# STM32F103-V1_0.net
KiCad netlist of a schematic drawn in Altium Designer
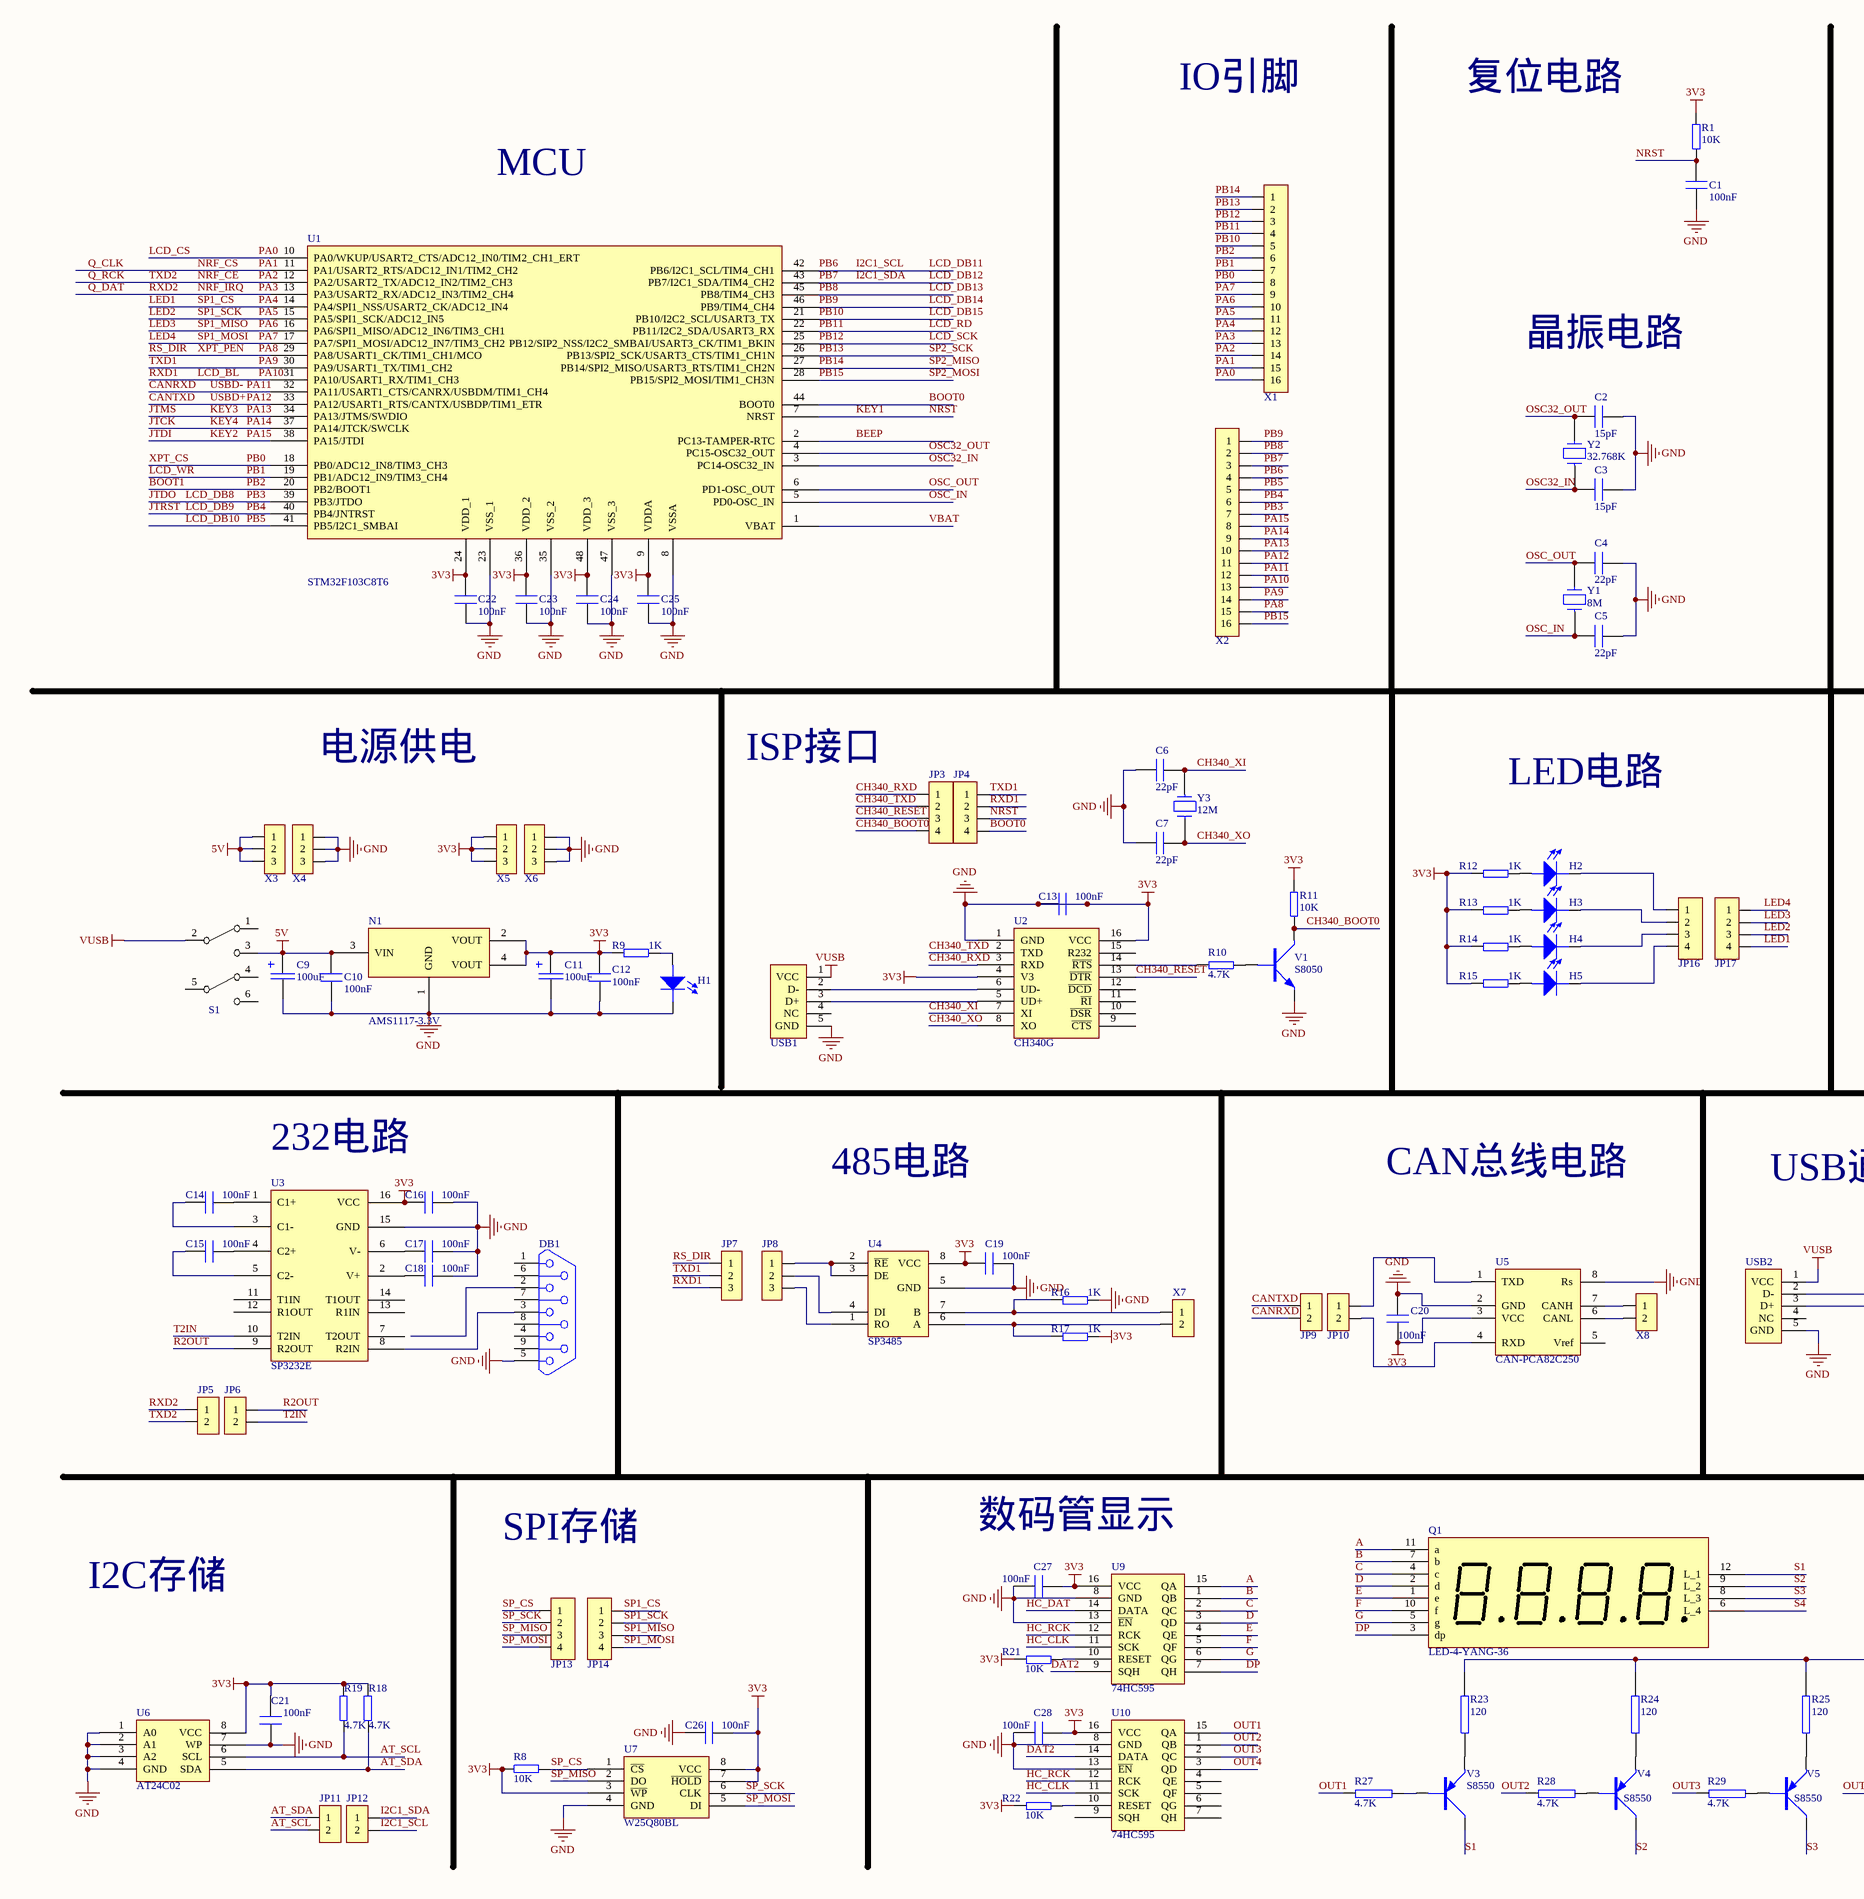
[diagram p0: STM32F103-V1.0.SchDoc, left]
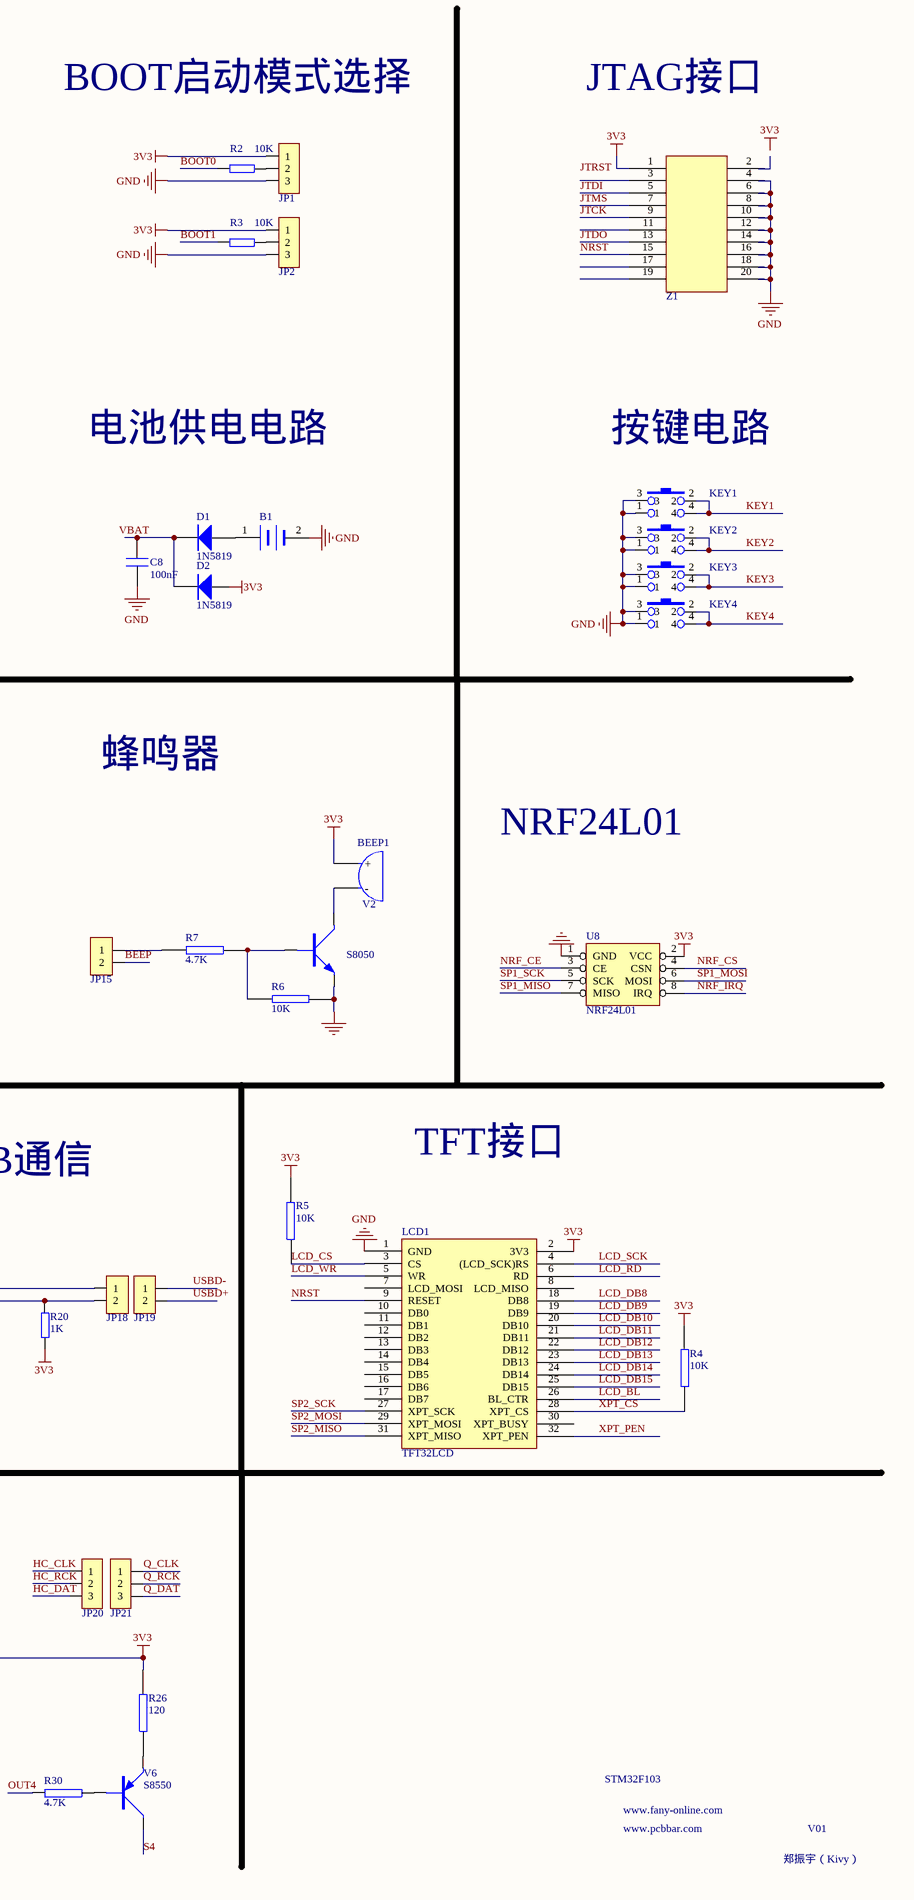
[diagram p1: STM32F103-V1.0.SchDoc, right]

(export (version "E")
  (design (tool "Eeschema 10.0.6"))
  (components
    (comp (ref "B1") (value "BATTERY") (footprint "CR1220") (libsource (lib "Liuzhx") (part "BATTERY")))
    (comp (ref "BEEP1") (value "BEEP") (footprint "SOT12-7.6") (libsource (lib "RationSTM32") (part "BEEP")))
    (comp (ref "C1")
      (value "100nF")
      (footprint "C0805")
      (description "Capacitor")
      (libsource (lib "Liuzhx") (part "普通贴片电容"))
    )
    (comp (ref "C2")
      (value "15pF")
      (footprint "C0805")
      (description "Capacitor")
      (libsource (lib "Liuzhx") (part "普通贴片电容"))
    )
    (comp (ref "C3") (value "15pF") (description "Capacitor") (libsource (lib "Liuzhx") (part "普通贴片电容")))
    (comp (ref "C4") (value "22pF") (description "Capacitor") (libsource (lib "Liuzhx") (part "普通贴片电容")))
    (comp (ref "C5") (value "22pF") (description "Capacitor") (libsource (lib "Liuzhx") (part "普通贴片电容")))
    (comp (ref "C6") (value "22pF") (description "Capacitor") (libsource (lib "Liuzhx") (part "普通贴片电容")))
    (comp (ref "C7")
      (value "22pF")
      (footprint "C0805")
      (description "Capacitor")
      (libsource (lib "Liuzhx") (part "普通贴片电容"))
    )
    (comp (ref "C8")
      (value "100nF")
      (footprint "C0805")
      (description "Capacitor")
      (libsource (lib "Liuzhx") (part "普通贴片电容"))
    )
    (comp (ref "C9") (value "100uF") (footprint "CAP5*5_4") (libsource (lib "Liuzhx") (part "极性电容器")))
    (comp (ref "C10")
      (value "100nF")
      (footprint "C0805")
      (description "Capacitor")
      (libsource (lib "Liuzhx") (part "普通贴片电容"))
    )
    (comp (ref "C11") (value "100uF") (footprint "CAP5*5_4") (libsource (lib "Liuzhx") (part "极性电容器")))
    (comp (ref "C12")
      (value "100nF")
      (footprint "C0805")
      (description "Capacitor")
      (libsource (lib "Liuzhx") (part "普通贴片电容"))
    )
    (comp (ref "C13")
      (value "100nF")
      (footprint "C0805")
      (description "Capacitor")
      (libsource (lib "Liuzhx") (part "普通贴片电容"))
    )
    (comp (ref "C14")
      (value "100nF")
      (footprint "C0805")
      (description "Capacitor")
      (libsource (lib "Liuzhx") (part "普通贴片电容"))
    )
    (comp (ref "C15")
      (value "100nF")
      (footprint "C0805")
      (description "Capacitor")
      (libsource (lib "Liuzhx") (part "普通贴片电容"))
    )
    (comp (ref "C16")
      (value "100nF")
      (footprint "C0805")
      (description "Capacitor")
      (libsource (lib "Liuzhx") (part "普通贴片电容"))
    )
    (comp (ref "C17")
      (value "100nF")
      (footprint "C0805")
      (description "Capacitor")
      (libsource (lib "Liuzhx") (part "普通贴片电容"))
    )
    (comp (ref "C18")
      (value "100nF")
      (footprint "C0805")
      (description "Capacitor")
      (libsource (lib "Liuzhx") (part "普通贴片电容"))
    )
    (comp (ref "C19")
      (value "100nF")
      (footprint "C0805")
      (description "Capacitor")
      (libsource (lib "Liuzhx") (part "普通贴片电容"))
    )
    (comp (ref "C20")
      (value "100nF")
      (footprint "C0805")
      (description "Capacitor")
      (libsource (lib "GKSSCH") (part "普通贴片电容"))
    )
    (comp (ref "C21")
      (value "100nF")
      (footprint "C0805")
      (description "Capacitor")
      (libsource (lib "Liuzhx") (part "普通贴片电容"))
    )
    (comp (ref "C22")
      (value "100nF")
      (footprint "C0805")
      (description "Capacitor")
      (libsource (lib "Liuzhx") (part "普通贴片电容"))
    )
    (comp (ref "C23")
      (value "100nF")
      (footprint "C0805")
      (description "Capacitor")
      (libsource (lib "Liuzhx") (part "普通贴片电容"))
    )
    (comp (ref "C24")
      (value "100nF")
      (footprint "C0805")
      (description "Capacitor")
      (libsource (lib "Liuzhx") (part "普通贴片电容"))
    )
    (comp (ref "C25")
      (value "100nF")
      (footprint "C0805")
      (description "Capacitor")
      (libsource (lib "Liuzhx") (part "普通贴片电容"))
    )
    (comp (ref "C26") (value "100nF") (description "Capacitor") (libsource (lib "Liuzhx") (part "普通贴片电容")))
    (comp (ref "C27") (value "100nF") (description "Capacitor") (libsource (lib "Liuzhx") (part "普通贴片电容")))
    (comp (ref "C28") (value "100nF") (description "Capacitor") (libsource (lib "Liuzhx") (part "普通贴片电容")))
    (comp (ref "D1")
      (value "1N5819")
      (footprint "1N4148-T")
      (description "Diode 1N series")
      (libsource (lib "Liuzhx") (part "贴片二极管"))
    )
    (comp (ref "D2")
      (value "1N5819")
      (footprint "1N4148-T")
      (description "Diode 1N series")
      (libsource (lib "Liuzhx") (part "贴片二极管"))
    )
    (comp (ref "DB1")
      (value "DB9M")
      (footprint "DB9-M")
      (description "母头")
      (libsource (lib "Liuzhx") (part "DB9M"))
    )
    (comp (ref "H1") (value "发光二极管") (footprint "LED1206") (libsource (lib "Liuzhx") (part "发光二极管")))
    (comp (ref "H2") (value "发光二极管") (footprint "LED1206") (libsource (lib "Liuzhx") (part "发光二极管")))
    (comp (ref "H3") (value "发光二极管") (footprint "LED1206") (libsource (lib "Liuzhx") (part "发光二极管")))
    (comp (ref "H4") (value "发光二极管") (footprint "LED1206") (libsource (lib "Liuzhx") (part "发光二极管")))
    (comp (ref "H5") (value "发光二极管") (footprint "LED1206") (libsource (lib "Liuzhx") (part "发光二极管")))
    (comp (ref "JP1")
      (value "JX3")
      (footprint "SIP3")
      (description "Connector")
      (libsource (lib "") (part "JX3_1"))
    )
    (comp (ref "JP2")
      (value "JX3")
      (footprint "SIP3")
      (description "Connector")
      (libsource (lib "") (part "JX3_1"))
    )
    (comp (ref "JP3")
      (value "JX4")
      (footprint "SIP4")
      (description "Connector")
      (libsource (lib "Liuzhx") (part "JX4"))
    )
    (comp (ref "JP4")
      (value "JX4")
      (footprint "SIP4")
      (description "Connector")
      (libsource (lib "") (part "JX4_1"))
    )
    (comp (ref "JP5")
      (value "JX2")
      (footprint "SIP2")
      (description "Connector")
      (libsource (lib "Liuzhx") (part "JX2"))
    )
    (comp (ref "JP6")
      (value "JX2")
      (footprint "SIP2")
      (description "Connector")
      (libsource (lib "") (part "JX2_1"))
    )
    (comp (ref "JP7")
      (value "JX3")
      (footprint "SIP3")
      (description "Connector")
      (libsource (lib "") (part "JX3_1"))
    )
    (comp (ref "JP8")
      (value "JX3")
      (footprint "SIP3")
      (description "Connector")
      (libsource (lib "Liuzhx") (part "JX3"))
    )
    (comp (ref "JP9")
      (value "JX2")
      (footprint "SIP2")
      (description "Connector")
      (libsource (lib "GKSSCH") (part "JX2"))
    )
    (comp (ref "JP10")
      (value "JX2")
      (footprint "SIP2")
      (description "Connector")
      (libsource (lib "") (part "JX2_1"))
    )
    (comp (ref "JP11")
      (value "JX2")
      (footprint "SIP2")
      (description "Connector")
      (libsource (lib "Liuzhx") (part "JX2"))
    )
    (comp (ref "JP12")
      (value "JX2")
      (footprint "SIP2")
      (description "Connector")
      (libsource (lib "") (part "JX2_1"))
    )
    (comp (ref "JP13")
      (value "JX4")
      (footprint "SIP4")
      (description "Connector")
      (libsource (lib "Liuzhx") (part "JX4"))
    )
    (comp (ref "JP14")
      (value "JX4")
      (footprint "SIP4")
      (description "Connector")
      (libsource (lib "") (part "JX4_1"))
    )
    (comp (ref "JP15")
      (value "JX2")
      (footprint "SIP2")
      (description "Connector")
      (libsource (lib "") (part "JX2_1"))
    )
    (comp (ref "JP16")
      (value "JX4")
      (footprint "SIP4")
      (description "Connector")
      (libsource (lib "Liuzhx") (part "JX4"))
    )
    (comp (ref "JP17")
      (value "JX4")
      (footprint "SIP4")
      (description "Connector")
      (libsource (lib "") (part "JX4_1"))
    )
    (comp (ref "JP18")
      (value "JX2")
      (footprint "SIP2")
      (description "Connector")
      (libsource (lib "Liuzhx") (part "JX2"))
    )
    (comp (ref "JP19")
      (value "JX2")
      (footprint "SIP2")
      (description "Connector")
      (libsource (lib "") (part "JX2_1"))
    )
    (comp (ref "JP20")
      (value "JX3")
      (footprint "SIP3")
      (description "Connector")
      (libsource (lib "") (part "JX3_1"))
    )
    (comp (ref "JP21")
      (value "JX3")
      (footprint "SIP3")
      (description "Connector")
      (libsource (lib "Liuzhx") (part "JX3"))
    )
    (comp (ref "KEY1")
      (value "SW-66B7")
      (footprint "STM32F103-V1.0:SW-66")
      (libsource (lib "Liuzhx") (part "SW-66B7"))
    )
    (comp (ref "KEY2")
      (value "SW-66B7")
      (footprint "STM32F103-V1.0:SW-66")
      (libsource (lib "Liuzhx") (part "SW-66B7"))
    )
    (comp (ref "KEY3")
      (value "SW-66B7")
      (footprint "STM32F103-V1.0:SW-66")
      (libsource (lib "Liuzhx") (part "SW-66B7"))
    )
    (comp (ref "KEY4")
      (value "SW-66B7")
      (footprint "STM32F103-V1.0:SW-66")
      (libsource (lib "Liuzhx") (part "SW-66B7"))
    )
    (comp (ref "LCD1") (value "TFT32LCD") (footprint "HEAD16×2") (libsource (lib "Liuzhx") (part "TFT32LCD")))
    (comp (ref "N1")
      (value "AMS1117-3.3V")
      (footprint "SOT223")
      (libsource (lib "Liuzhx") (part "AMS1117-3.3V"))
    )
    (comp (ref "Q1")
      (value "LED-4-YANG-36")
      (footprint "LED0:LED0.36-4")
      (libsource (lib "Liuzhx") (part "LED-4-YANG-36"))
    )
    (comp (ref "R1") (value "10K") (libsource (lib "Liuzhx") (part "普通贴片电阻")))
    (comp (ref "R2") (value "10K") (footprint "R0805") (libsource (lib "Liuzhx") (part "普通贴片电阻")))
    (comp (ref "R3") (value "10K") (footprint "R0805") (libsource (lib "Liuzhx") (part "普通贴片电阻")))
    (comp (ref "R4") (value "10K") (footprint "R0805") (libsource (lib "RationSTM32") (part "RES")))
    (comp (ref "R5") (value "10K") (footprint "R0805") (libsource (lib "RationSTM32") (part "RES")))
    (comp (ref "R6") (value "10K") (footprint "R0805") (libsource (lib "RationSTM32") (part "RES")))
    (comp (ref "R7") (value "4.7K") (footprint "R0805") (libsource (lib "RationSTM32") (part "RES")))
    (comp (ref "R8") (value "10K") (footprint "R0805") (libsource (lib "Liuzhx") (part "普通贴片电阻")))
    (comp (ref "R9") (value "1K") (footprint "R0805") (libsource (lib "Liuzhx") (part "普通贴片电阻")))
    (comp (ref "R10") (value "4.7K") (libsource (lib "Liuzhx") (part "普通贴片电阻")))
    (comp (ref "R11") (value "10K") (libsource (lib "Liuzhx") (part "普通贴片电阻")))
    (comp (ref "R12") (value "1K") (libsource (lib "Liuzhx") (part "普通贴片电阻")))
    (comp (ref "R13") (value "1K") (libsource (lib "Liuzhx") (part "普通贴片电阻")))
    (comp (ref "R14") (value "1K") (footprint "R0805") (libsource (lib "Liuzhx") (part "普通贴片电阻")))
    (comp (ref "R15") (value "1K") (footprint "R0805") (libsource (lib "Liuzhx") (part "普通贴片电阻")))
    (comp (ref "R16") (value "1K") (footprint "R0805") (libsource (lib "Liuzhx") (part "普通贴片电阻")))
    (comp (ref "R17") (value "1K") (footprint "R0805") (libsource (lib "Liuzhx") (part "普通贴片电阻")))
    (comp (ref "R18") (value "4.7K") (footprint "R0805") (libsource (lib "Liuzhx") (part "普通贴片电阻")))
    (comp (ref "R19") (value "4.7K") (footprint "R0805") (libsource (lib "Liuzhx") (part "普通贴片电阻")))
    (comp (ref "R20") (value "1K") (footprint "R0805") (libsource (lib "Liuzhx") (part "普通贴片电阻")))
    (comp (ref "R21") (value "10K") (footprint "R0805") (libsource (lib "Liuzhx") (part "普通贴片电阻")))
    (comp (ref "R22") (value "10K") (footprint "R0805") (libsource (lib "Liuzhx") (part "普通贴片电阻")))
    (comp (ref "R23") (value "120") (footprint "R0805") (libsource (lib "STM32F103-V1.0") (part "RES")))
    (comp (ref "R24") (value "120") (footprint "R0805") (libsource (lib "STM32F103-V1.0") (part "RES")))
    (comp (ref "R25") (value "120") (footprint "R0805") (libsource (lib "STM32F103-V1.0") (part "RES")))
    (comp (ref "R26") (value "120") (footprint "R0805") (libsource (lib "STM32F103-V1.0") (part "RES")))
    (comp (ref "R27") (value "4.7K") (footprint "R0805") (libsource (lib "STM32F103-V1.0") (part "RES2")))
    (comp (ref "R28") (value "4.7K") (footprint "R0805") (libsource (lib "STM32F103-V1.0") (part "RES2")))
    (comp (ref "R29") (value "4.7K") (footprint "R0805") (libsource (lib "STM32F103-V1.0") (part "RES2")))
    (comp (ref "R30") (value "4.7K") (footprint "R0805") (libsource (lib "STM32F103-V1.0") (part "RES2")))
    (comp (ref "S1") (value "SWITCH-6") (footprint "SW-AJ") (libsource (lib "Liuzhx") (part "SWITCH-6")))
    (comp (ref "U1")
      (value "STM32F103C8T6")
      (footprint "LQFP48")
      (libsource (lib "STM32F103-V1.0") (part "STM32F103C8T6"))
    )
    (comp (ref "U2")
      (value "CH340G")
      (footprint "STM32F103-V1.0:SOIC16")
      (libsource (lib "Liuzhx") (part "CH340G"))
    )
    (comp (ref "U3")
      (value "SP3232E")
      (footprint "SOIC16")
      (description "SP3232EEN-L/TR;SOIC-39MM")
      (libsource (lib "Liuzhx") (part "SP3232E"))
    )
    (comp (ref "U4") (value "SP3485") (footprint "SO-8") (libsource (lib "Liuzhx") (part "MAX3082")))
    (comp (ref "U5")
      (value "CAN-PCA82C250")
      (footprint "SO-8")
      (libsource (lib "GKSSCH") (part "CAN-PCA82C250"))
    )
    (comp (ref "U6") (value "AT24C02") (footprint "SO-8") (libsource (lib "Liuzhx") (part "AT24C02")))
    (comp (ref "U7") (value "W25Q80BL") (footprint "W25Q-SO8") (libsource (lib "Liuzhx") (part "W25Q80BL")))
    (comp (ref "U8") (value "NRF24L01") (footprint "NRF24L01") (libsource (lib "Liuzhx") (part "NRF24L01")))
    (comp (ref "U9")
      (value "74HC595")
      (footprint "SO-16")
      (description "串入并出移位寄存器")
      (libsource (lib "Liuzhx") (part "74HC595"))
    )
    (comp (ref "U10")
      (value "74HC595")
      (footprint "SO-16")
      (description "串入并出移位寄存器")
      (libsource (lib "Liuzhx") (part "74HC595"))
    )
    (comp (ref "USB1")
      (value "MicroUSB")
      (footprint "MicroUSB1")
      (description "母头")
      (libsource (lib "Liuzhx") (part "MicroUSB"))
    )
    (comp (ref "USB2")
      (value "MicroUSB")
      (footprint "MicroUSB1")
      (description "母头")
      (libsource (lib "Liuzhx") (part "MicroUSB"))
    )
    (comp (ref "V1")
      (value "S8050")
      (footprint "SOT23-C1")
      (description "V")
      (libsource (lib "Liuzhx") (part "NPN三极管"))
    )
    (comp (ref "V2")
      (value "S8050")
      (footprint "SOT23-C1")
      (description "V")
      (libsource (lib "Liuzhx") (part "NPN三极管"))
    )
    (comp (ref "V3")
      (value "S8550")
      (footprint "SOT23-C1")
      (description "V")
      (libsource (lib "*") (part "PNP三极管"))
    )
    (comp (ref "V4")
      (value "S8550")
      (footprint "SOT23-C1")
      (description "V")
      (libsource (lib "*") (part "PNP三极管"))
    )
    (comp (ref "V5")
      (value "S8550")
      (footprint "SOT23-C1")
      (description "V")
      (libsource (lib "*") (part "PNP三极管"))
    )
    (comp (ref "V6")
      (value "S8550")
      (footprint "SOT23-C1")
      (description "V")
      (libsource (lib "*") (part "PNP三极管"))
    )
    (comp (ref "X1") (value "JX16") (footprint "SIP16") (libsource (lib "Liuzhx") (part "JX16")))
    (comp (ref "X2") (value "JX16") (footprint "SIP16") (libsource (lib "") (part "JX16_1")))
    (comp (ref "X3")
      (value "JX3")
      (footprint "SIP3")
      (description "Connector")
      (libsource (lib "") (part "JX3_1"))
    )
    (comp (ref "X4")
      (value "JX3")
      (footprint "SIP3")
      (description "Connector")
      (libsource (lib "Liuzhx") (part "JX3"))
    )
    (comp (ref "X5")
      (value "JX3")
      (footprint "SIP3")
      (description "Connector")
      (libsource (lib "") (part "JX3_1"))
    )
    (comp (ref "X6")
      (value "JX3")
      (footprint "SIP3")
      (description "Connector")
      (libsource (lib "Liuzhx") (part "JX3"))
    )
    (comp (ref "X7")
      (value "JX2")
      (footprint "WJ128-5.0-2P")
      (description "Connector")
      (libsource (lib "Liuzhx") (part "JX2"))
    )
    (comp (ref "X8")
      (value "JX2")
      (footprint "WJ128-5.0-2P")
      (description "Connector")
      (libsource (lib "GKSSCH") (part "JX2"))
    )
    (comp (ref "Y1")
      (value "8M")
      (footprint "JZ-AX")
      (description "Crystal")
      (libsource (lib "Liuzhx") (part "CRYSTAL"))
    )
    (comp (ref "Y2")
      (value "32.768K")
      (footprint "FC135")
      (description "Crystal")
      (libsource (lib "Liuzhx") (part "CRYSTAL"))
    )
    (comp (ref "Y3")
      (value "12M")
      (footprint "JZ-AX")
      (description "Crystal")
      (libsource (lib "Liuzhx") (part "CRYSTAL"))
    )
    (comp (ref "Z1")
      (value "HEADER 10X2")
      (footprint "JTAG")
      (libsource (lib "STM32F103-V1.0") (part "HEADER 10X2"))
    )
  )
  (nets
    (net (code "1") (name "/A") (class "Default")
      (node (ref "Q1") (pin "11") (pinfunction "a_11") (pintype "passive"))
      (node (ref "U9") (pin "15") (pinfunction "QA_15") (pintype "passive"))
    )
    (net (code "2") (name "/AT_SCL") (class "Default")
      (node (ref "JP11") (pin "2") (pinfunction "2_2") (pintype "passive"))
      (node (ref "R19") (pin "1") (pinfunction "1_1") (pintype "passive"))
      (node (ref "U6") (pin "6") (pinfunction "SCL_6") (pintype "passive"))
    )
    (net (code "3") (name "/AT_SDA") (class "Default")
      (node (ref "JP11") (pin "1") (pinfunction "1_1") (pintype "passive"))
      (node (ref "R18") (pin "1") (pinfunction "1_1") (pintype "passive"))
      (node (ref "U6") (pin "5") (pinfunction "SDA_5") (pintype "passive"))
    )
    (net (code "4") (name "/B") (class "Default")
      (node (ref "Q1") (pin "7") (pinfunction "b_7") (pintype "passive"))
      (node (ref "U9") (pin "1") (pinfunction "QB_1") (pintype "passive"))
    )
    (net (code "5") (name "/BEEP") (class "Default")
      (node (ref "JP15") (pin "2") (pinfunction "2_2") (pintype "passive"))
      (node (ref "U1") (pin "2") (pinfunction "PC13-TAMPER-RTC_2") (pintype "passive"))
    )
    (net (code "6") (name "/BOOT0") (class "Default")
      (node (ref "JP4") (pin "4") (pinfunction "4_4") (pintype "passive"))
      (node (ref "R2") (pin "1") (pinfunction "1_1") (pintype "passive"))
      (node (ref "U1") (pin "44") (pinfunction "BOOT0_44") (pintype "passive"))
    )
    (net (code "7") (name "/BOOT1") (class "Default")
      (node (ref "R3") (pin "1") (pinfunction "1_1") (pintype "passive"))
      (node (ref "U1") (pin "20") (pinfunction "PB2/BOOT1_20") (pintype "passive"))
      (node (ref "X1") (pin "6") (pinfunction "6_6") (pintype "passive"))
    )
    (net (code "8") (name "/C") (class "Default")
      (node (ref "Q1") (pin "4") (pinfunction "c_4") (pintype "passive"))
      (node (ref "U9") (pin "2") (pinfunction "QC_2") (pintype "passive"))
    )
    (net (code "9") (name "/CANRXD") (class "Default")
      (node (ref "JP19") (pin "1") (pinfunction "1_1") (pintype "passive"))
      (node (ref "JP9") (pin "2") (pinfunction "2_2") (pintype "passive"))
      (node (ref "U1") (pin "32") (pinfunction "PA11/USART1_CTS/CANRX/USBDM/TIM1_CH4_32") (pintype "passive"))
      (node (ref "X2") (pin "12") (pinfunction "12_12") (pintype "passive"))
    )
    (net (code "10") (name "/CANTXD") (class "Default")
      (node (ref "JP19") (pin "2") (pinfunction "2_2") (pintype "passive"))
      (node (ref "JP9") (pin "1") (pinfunction "1_1") (pintype "passive"))
      (node (ref "U1") (pin "33") (pinfunction "PA12/USART1_RTS/CANTX/USBDP/TIM1_ETR_33") (pintype "passive"))
      (node (ref "X2") (pin "11") (pinfunction "11_11") (pintype "passive"))
    )
    (net (code "11") (name "/CH340_BOOT0") (class "Default")
      (node (ref "JP3") (pin "4") (pinfunction "4_4") (pintype "passive"))
      (node (ref "R11") (pin "1") (pinfunction "1_1") (pintype "passive"))
      (node (ref "V1") (pin "C") (pinfunction "C_C") (pintype "passive"))
    )
    (net (code "12") (name "/CH340_RESET") (class "Default")
      (node (ref "JP3") (pin "3") (pinfunction "3_3") (pintype "passive"))
      (node (ref "U2") (pin "13") (pinfunction "~{DTR}_13") (pintype "passive"))
    )
    (net (code "13") (name "/CH340_RXD") (class "Default")
      (node (ref "JP3") (pin "1") (pinfunction "1_1") (pintype "passive"))
      (node (ref "U2") (pin "3") (pinfunction "RXD_3") (pintype "passive"))
    )
    (net (code "14") (name "/CH340_TXD") (class "Default")
      (node (ref "JP3") (pin "2") (pinfunction "2_2") (pintype "passive"))
      (node (ref "U2") (pin "2") (pinfunction "TXD_2") (pintype "passive"))
    )
    (net (code "15") (name "/CH340_XI") (class "Default")
      (node (ref "C6") (pin "2") (pinfunction "2_2") (pintype "passive"))
      (node (ref "U2") (pin "7") (pinfunction "XI_7") (pintype "passive"))
      (node (ref "Y3") (pin "1") (pinfunction "1_1") (pintype "passive"))
    )
    (net (code "16") (name "/CH340_XO") (class "Default")
      (node (ref "C7") (pin "2") (pinfunction "2_2") (pintype "passive"))
      (node (ref "U2") (pin "8") (pinfunction "XO_8") (pintype "passive"))
      (node (ref "Y3") (pin "2") (pinfunction "2_2") (pintype "passive"))
    )
    (net (code "17") (name "/D") (class "Default")
      (node (ref "Q1") (pin "2") (pinfunction "d_2") (pintype "passive"))
      (node (ref "U9") (pin "3") (pinfunction "QD_3") (pintype "passive"))
    )
    (net (code "18") (name "/DAT2") (class "Default")
      (node (ref "U10") (pin "14") (pinfunction "DATA_14") (pintype "passive"))
      (node (ref "U9") (pin "9") (pinfunction "SQH_9") (pintype "passive"))
    )
    (net (code "19") (name "/DP") (class "Default")
      (node (ref "Q1") (pin "3") (pinfunction "dp_3") (pintype "passive"))
      (node (ref "U9") (pin "7") (pinfunction "QH_7") (pintype "passive"))
    )
    (net (code "20") (name "/E") (class "Default")
      (node (ref "Q1") (pin "1") (pinfunction "e_1") (pintype "passive"))
      (node (ref "U9") (pin "4") (pinfunction "QE_4") (pintype "passive"))
    )
    (net (code "21") (name "/F") (class "Default")
      (node (ref "Q1") (pin "10") (pinfunction "f_10") (pintype "passive"))
      (node (ref "U9") (pin "5") (pinfunction "QF_5") (pintype "passive"))
    )
    (net (code "22") (name "/G") (class "Default")
      (node (ref "Q1") (pin "5") (pinfunction "g_5") (pintype "passive"))
      (node (ref "U9") (pin "6") (pinfunction "QG_6") (pintype "passive"))
    )
    (net (code "23") (name "/HC_CLK") (class "Default")
      (node (ref "JP20") (pin "1") (pinfunction "1_1") (pintype "passive"))
      (node (ref "U10") (pin "11") (pinfunction "SCK_11") (pintype "passive"))
      (node (ref "U9") (pin "11") (pinfunction "SCK_11") (pintype "passive"))
    )
    (net (code "24") (name "/HC_DAT") (class "Default")
      (node (ref "JP20") (pin "3") (pinfunction "3_3") (pintype "passive"))
      (node (ref "U9") (pin "14") (pinfunction "DATA_14") (pintype "passive"))
    )
    (net (code "25") (name "/HC_RCK") (class "Default")
      (node (ref "JP20") (pin "2") (pinfunction "2_2") (pintype "passive"))
      (node (ref "U10") (pin "12") (pinfunction "RCK_12") (pintype "passive"))
      (node (ref "U9") (pin "12") (pinfunction "RCK_12") (pintype "passive"))
    )
    (net (code "26") (name "/I2C1_SCL") (class "Default")
      (node (ref "JP12") (pin "2") (pinfunction "2_2") (pintype "passive"))
      (node (ref "LCD1") (pin "21") (pinfunction "DB11_21") (pintype "passive"))
      (node (ref "U1") (pin "42") (pinfunction "PB6/I2C1_SCL/TIM4_CH1_42") (pintype "passive"))
      (node (ref "X2") (pin "4") (pinfunction "4_4") (pintype "passive"))
    )
    (net (code "27") (name "/I2C1_SDA") (class "Default")
      (node (ref "JP12") (pin "1") (pinfunction "1_1") (pintype "passive"))
      (node (ref "LCD1") (pin "22") (pinfunction "DB12_22") (pintype "passive"))
      (node (ref "U1") (pin "43") (pinfunction "PB7/I2C1_SDA/TIM4_CH2_43") (pintype "passive"))
      (node (ref "X2") (pin "3") (pinfunction "3_3") (pintype "passive"))
    )
    (net (code "28") (name "/JTCK") (class "Default")
      (node (ref "KEY4") (pin "2") (pinfunction "2_2") (pintype "passive"))
      (node (ref "KEY4") (pin "4") (pinfunction "4_4") (pintype "passive"))
      (node (ref "U1") (pin "37") (pinfunction "PA14/JTCK/SWCLK_37") (pintype "passive"))
      (node (ref "X2") (pin "9") (pinfunction "9_9") (pintype "passive"))
      (node (ref "Z1") (pin "9") (pinfunction "9_9") (pintype "passive"))
    )
    (net (code "29") (name "/JTDI") (class "Default")
      (node (ref "KEY2") (pin "2") (pinfunction "2_2") (pintype "passive"))
      (node (ref "KEY2") (pin "4") (pinfunction "4_4") (pintype "passive"))
      (node (ref "U1") (pin "38") (pinfunction "PA15/JTDI_38") (pintype "passive"))
      (node (ref "X2") (pin "8") (pinfunction "8_8") (pintype "passive"))
      (node (ref "Z1") (pin "5") (pinfunction "5_5") (pintype "passive"))
    )
    (net (code "30") (name "/JTDO") (class "Default")
      (node (ref "LCD1") (pin "18") (pinfunction "DB8_18") (pintype "passive"))
      (node (ref "U1") (pin "39") (pinfunction "PB3/JTDO_39") (pintype "passive"))
      (node (ref "X2") (pin "7") (pinfunction "7_7") (pintype "passive"))
      (node (ref "Z1") (pin "13") (pinfunction "13_13") (pintype "passive"))
    )
    (net (code "31") (name "/JTMS") (class "Default")
      (node (ref "KEY3") (pin "2") (pinfunction "2_2") (pintype "passive"))
      (node (ref "KEY3") (pin "4") (pinfunction "4_4") (pintype "passive"))
      (node (ref "U1") (pin "34") (pinfunction "PA13/JTMS/SWDIO_34") (pintype "passive"))
      (node (ref "X2") (pin "10") (pinfunction "10_10") (pintype "passive"))
      (node (ref "Z1") (pin "7") (pinfunction "7_7") (pintype "passive"))
    )
    (net (code "32") (name "/JTRST") (class "Default")
      (node (ref "LCD1") (pin "19") (pinfunction "DB9_19") (pintype "passive"))
      (node (ref "U1") (pin "40") (pinfunction "PB4/JNTRST_40") (pintype "passive"))
      (node (ref "X2") (pin "6") (pinfunction "6_6") (pintype "passive"))
    )
    (net (code "33") (name "/KEY1") (class "Default")
      (node (ref "C1") (pin "2") (pinfunction "2_2") (pintype "passive"))
      (node (ref "JP4") (pin "3") (pinfunction "3_3") (pintype "passive"))
      (node (ref "KEY1") (pin "2") (pinfunction "2_2") (pintype "passive"))
      (node (ref "KEY1") (pin "4") (pinfunction "4_4") (pintype "passive"))
      (node (ref "LCD1") (pin "9") (pinfunction "RESET_9") (pintype "passive"))
      (node (ref "R1") (pin "1") (pinfunction "1_1") (pintype "passive"))
      (node (ref "U1") (pin "7") (pinfunction "NRST_7") (pintype "passive"))
      (node (ref "Z1") (pin "15") (pinfunction "15_15") (pintype "passive"))
    )
    (net (code "34") (name "/LCD_BL") (class "Default")
      (node (ref "JP4") (pin "2") (pinfunction "2_2") (pintype "passive"))
      (node (ref "JP7") (pin "3") (pinfunction "3_3") (pintype "passive"))
      (node (ref "LCD1") (pin "26") (pinfunction "BL_CTR_26") (pintype "passive"))
      (node (ref "U1") (pin "31") (pinfunction "PA10/USART1_RX/TIM1_CH3_31") (pintype "passive"))
      (node (ref "X2") (pin "13") (pinfunction "13_13") (pintype "passive"))
    )
    (net (code "35") (name "/LCD_CS") (class "Default")
      (node (ref "LCD1") (pin "3") (pinfunction "CS_3") (pintype "passive"))
      (node (ref "R5") (pin "1") (pinfunction "1_1") (pintype "passive"))
      (node (ref "U1") (pin "10") (pinfunction "PA0/WKUP/USART2_CTS/ADC12_IN0/TIM2_CH1_ERT_10") (pintype "passive"))
      (node (ref "X1") (pin "16") (pinfunction "16_16") (pintype "passive"))
    )
    (net (code "36") (name "/LCD_DB10") (class "Default")
      (node (ref "LCD1") (pin "20") (pinfunction "DB10_20") (pintype "passive"))
      (node (ref "U1") (pin "41") (pinfunction "PB5/I2C1_SMBAI_41") (pintype "passive"))
      (node (ref "X2") (pin "5") (pinfunction "5_5") (pintype "passive"))
    )
    (net (code "37") (name "/LCD_DB13") (class "Default")
      (node (ref "LCD1") (pin "23") (pinfunction "DB13_23") (pintype "passive"))
      (node (ref "U1") (pin "45") (pinfunction "PB8/TIM4_CH3_45") (pintype "passive"))
      (node (ref "X2") (pin "2") (pinfunction "2_2") (pintype "passive"))
    )
    (net (code "38") (name "/LCD_DB14") (class "Default")
      (node (ref "LCD1") (pin "24") (pinfunction "DB14_24") (pintype "passive"))
      (node (ref "U1") (pin "46") (pinfunction "PB9/TIM4_CH4_46") (pintype "passive"))
      (node (ref "X2") (pin "1") (pinfunction "1_1") (pintype "passive"))
    )
    (net (code "39") (name "/LCD_DB15") (class "Default")
      (node (ref "LCD1") (pin "25") (pinfunction "DB15_25") (pintype "passive"))
      (node (ref "U1") (pin "21") (pinfunction "PB10/I2C2_SCL/USART3_TX_21") (pintype "passive"))
      (node (ref "X1") (pin "5") (pinfunction "5_5") (pintype "passive"))
    )
    (net (code "40") (name "/LCD_RD") (class "Default")
      (node (ref "LCD1") (pin "6") (pinfunction "RD_6") (pintype "passive"))
      (node (ref "U1") (pin "22") (pinfunction "PB11/I2C2_SDA/USART3_RX_22") (pintype "passive"))
      (node (ref "X1") (pin "4") (pinfunction "4_4") (pintype "passive"))
    )
    (net (code "41") (name "/LCD_SCK") (class "Default")
      (node (ref "LCD1") (pin "4") (pinfunction "(LCD_SCK)RS_4") (pintype "passive"))
      (node (ref "U1") (pin "25") (pinfunction "PB12/SIP2_NSS/I2C2_SMBAI/USART3_CK/TIM1_BKIN_25") (pintype "passive"))
      (node (ref "X1") (pin "3") (pinfunction "3_3") (pintype "passive"))
    )
    (net (code "42") (name "/LCD_WR") (class "Default")
      (node (ref "LCD1") (pin "5") (pinfunction "WR_5") (pintype "passive"))
      (node (ref "U1") (pin "19") (pinfunction "PB1/ADC12_IN9/TIM3_CH4_19") (pintype "passive"))
      (node (ref "X1") (pin "7") (pinfunction "7_7") (pintype "passive"))
    )
    (net (code "43") (name "/LED1") (class "Default")
      (node (ref "JP14") (pin "1") (pinfunction "1_1") (pintype "passive"))
      (node (ref "JP17") (pin "4") (pinfunction "4_4") (pintype "passive"))
      (node (ref "U1") (pin "14") (pinfunction "PA4/SPI1_NSS/USART2_CK/ADC12_IN4_14") (pintype "passive"))
      (node (ref "X1") (pin "12") (pinfunction "12_12") (pintype "passive"))
    )
    (net (code "44") (name "/LED2") (class "Default")
      (node (ref "JP14") (pin "2") (pinfunction "2_2") (pintype "passive"))
      (node (ref "JP17") (pin "3") (pinfunction "3_3") (pintype "passive"))
      (node (ref "U1") (pin "15") (pinfunction "PA5/SPI1_SCK/ADC12_IN5_15") (pintype "passive"))
      (node (ref "U8") (pin "5") (pinfunction "SCK_5") (pintype "passive"))
      (node (ref "X1") (pin "11") (pinfunction "11_11") (pintype "passive"))
    )
    (net (code "45") (name "/LED3") (class "Default")
      (node (ref "JP14") (pin "3") (pinfunction "3_3") (pintype "passive"))
      (node (ref "JP17") (pin "2") (pinfunction "2_2") (pintype "passive"))
      (node (ref "U1") (pin "16") (pinfunction "PA6/SPI1_MISO/ADC12_IN6/TIM3_CH1_16") (pintype "passive"))
      (node (ref "U8") (pin "7") (pinfunction "MISO_7") (pintype "passive"))
      (node (ref "X1") (pin "10") (pinfunction "10_10") (pintype "passive"))
    )
    (net (code "46") (name "/LED4") (class "Default")
      (node (ref "JP14") (pin "4") (pinfunction "4_4") (pintype "passive"))
      (node (ref "JP17") (pin "1") (pinfunction "1_1") (pintype "passive"))
      (node (ref "U1") (pin "17") (pinfunction "PA7/SPI1_MOSI/ADC12_IN7/TIM3_CH2_17") (pintype "passive"))
      (node (ref "U8") (pin "6") (pinfunction "MOSI_6") (pintype "passive"))
      (node (ref "X1") (pin "9") (pinfunction "9_9") (pintype "passive"))
    )
    (net (code "47") (name "/NRF_CE") (class "Default")
      (node (ref "JP21") (pin "2") (pinfunction "2_2") (pintype "passive"))
      (node (ref "JP5") (pin "2") (pinfunction "2_2") (pintype "passive"))
      (node (ref "U1") (pin "12") (pinfunction "PA2/USART2_TX/ADC12_IN2/TIM2_CH3_12") (pintype "passive"))
      (node (ref "U8") (pin "3") (pinfunction "CE_3") (pintype "passive"))
      (node (ref "X1") (pin "14") (pinfunction "14_14") (pintype "passive"))
    )
    (net (code "48") (name "/NRF_CS") (class "Default")
      (node (ref "JP21") (pin "1") (pinfunction "1_1") (pintype "passive"))
      (node (ref "U1") (pin "11") (pinfunction "PA1/USART2_RTS/ADC12_IN1/TIM2_CH2_11") (pintype "passive"))
      (node (ref "U8") (pin "4") (pinfunction "CSN_4") (pintype "passive"))
      (node (ref "X1") (pin "15") (pinfunction "15_15") (pintype "passive"))
    )
    (net (code "49") (name "/NRF_IRQ") (class "Default")
      (node (ref "JP21") (pin "3") (pinfunction "3_3") (pintype "passive"))
      (node (ref "JP5") (pin "1") (pinfunction "1_1") (pintype "passive"))
      (node (ref "U1") (pin "13") (pinfunction "PA3/USART2_RX/ADC12_IN3/TIM2_CH4_13") (pintype "passive"))
      (node (ref "U8") (pin "8") (pinfunction "IRQ_8") (pintype "passive"))
      (node (ref "X1") (pin "13") (pinfunction "13_13") (pintype "passive"))
    )
    (net (code "50") (name "/OSC32_IN") (class "Default")
      (node (ref "C3") (pin "1") (pinfunction "1_1") (pintype "passive"))
      (node (ref "U1") (pin "3") (pinfunction "PC14-OSC32_IN_3") (pintype "passive"))
      (node (ref "Y2") (pin "1") (pinfunction "1_1") (pintype "passive"))
    )
    (net (code "51") (name "/OSC32_OUT") (class "Default")
      (node (ref "C2") (pin "1") (pinfunction "1_1") (pintype "passive"))
      (node (ref "U1") (pin "4") (pinfunction "PC15-OSC32_OUT_4") (pintype "passive"))
      (node (ref "Y2") (pin "2") (pinfunction "2_2") (pintype "passive"))
    )
    (net (code "52") (name "/OSC_IN") (class "Default")
      (node (ref "C5") (pin "1") (pinfunction "1_1") (pintype "passive"))
      (node (ref "U1") (pin "5") (pinfunction "PD0-OSC_IN_5") (pintype "passive"))
      (node (ref "Y1") (pin "1") (pinfunction "1_1") (pintype "passive"))
    )
    (net (code "53") (name "/OSC_OUT") (class "Default")
      (node (ref "C4") (pin "1") (pinfunction "1_1") (pintype "passive"))
      (node (ref "U1") (pin "6") (pinfunction "PD1-OSC_OUT_6") (pintype "passive"))
      (node (ref "Y1") (pin "2") (pinfunction "2_2") (pintype "passive"))
    )
    (net (code "54") (name "/OUT1") (class "Default")
      (node (ref "R27") (pin "1") (pintype "passive"))
      (node (ref "U10") (pin "15") (pinfunction "QA_15") (pintype "passive"))
    )
    (net (code "55") (name "/OUT2") (class "Default")
      (node (ref "R28") (pin "1") (pintype "passive"))
      (node (ref "U10") (pin "1") (pinfunction "QB_1") (pintype "passive"))
    )
    (net (code "56") (name "/OUT3") (class "Default")
      (node (ref "R29") (pin "1") (pintype "passive"))
      (node (ref "U10") (pin "2") (pinfunction "QC_2") (pintype "passive"))
    )
    (net (code "57") (name "/OUT4") (class "Default")
      (node (ref "R30") (pin "1") (pintype "passive"))
      (node (ref "U10") (pin "3") (pinfunction "QD_3") (pintype "passive"))
    )
    (net (code "58") (name "/PA8") (class "Default")
      (node (ref "JP7") (pin "1") (pinfunction "1_1") (pintype "passive"))
      (node (ref "LCD1") (pin "32") (pinfunction "XPT_PEN_32") (pintype "passive"))
      (node (ref "U1") (pin "29") (pinfunction "PA8/USART1_CK/TIM1_CH1/MCO_29") (pintype "passive"))
      (node (ref "X2") (pin "15") (pinfunction "15_15") (pintype "passive"))
    )
    (net (code "59") (name "/PA9") (class "Default")
      (node (ref "JP4") (pin "1") (pinfunction "1_1") (pintype "passive"))
      (node (ref "JP7") (pin "2") (pinfunction "2_2") (pintype "passive"))
      (node (ref "U1") (pin "30") (pinfunction "PA9/USART1_TX/TIM1_CH2_30") (pintype "passive"))
      (node (ref "X2") (pin "14") (pinfunction "14_14") (pintype "passive"))
    )
    (net (code "60") (name "/PB0") (class "Default")
      (node (ref "LCD1") (pin "28") (pinfunction "XPT_CS_28") (pintype "passive"))
      (node (ref "R4") (pin "2") (pinfunction "2_2") (pintype "passive"))
      (node (ref "U1") (pin "18") (pinfunction "PB0/ADC12_IN8/TIM3_CH3_18") (pintype "passive"))
      (node (ref "X1") (pin "8") (pinfunction "8_8") (pintype "passive"))
    )
    (net (code "61") (name "/PB13") (class "Default")
      (node (ref "LCD1") (pin "27") (pinfunction "XPT_SCK_27") (pintype "passive"))
      (node (ref "U1") (pin "26") (pinfunction "PB13/SPI2_SCK/USART3_CTS/TIM1_CH1N_26") (pintype "passive"))
      (node (ref "X1") (pin "2") (pinfunction "2_2") (pintype "passive"))
    )
    (net (code "62") (name "/PB14") (class "Default")
      (node (ref "LCD1") (pin "31") (pinfunction "XPT_MISO_31") (pintype "passive"))
      (node (ref "U1") (pin "27") (pinfunction "PB14/SPI2_MISO/USART3_RTS/TIM1_CH2N_27") (pintype "passive"))
      (node (ref "X1") (pin "1") (pinfunction "1_1") (pintype "passive"))
    )
    (net (code "63") (name "/PB15") (class "Default")
      (node (ref "LCD1") (pin "29") (pinfunction "XPT_MOSI_29") (pintype "passive"))
      (node (ref "U1") (pin "28") (pinfunction "PB15/SPI2_MOSI/TIM1_CH3N_28") (pintype "passive"))
      (node (ref "X2") (pin "16") (pinfunction "16_16") (pintype "passive"))
    )
    (net (code "64") (name "/R2OUT") (class "Default")
      (node (ref "JP6") (pin "1") (pinfunction "1_1") (pintype "passive"))
      (node (ref "U3") (pin "9") (pinfunction "R2OUT_9") (pintype "passive"))
    )
    (net (code "65") (name "/S1") (class "Default")
      (node (ref "Q1") (pin "12") (pinfunction "L_1_12") (pintype "passive"))
      (node (ref "V3") (pin "C") (pinfunction "C_C") (pintype "passive"))
    )
    (net (code "66") (name "/S2") (class "Default")
      (node (ref "Q1") (pin "9") (pinfunction "L_2_9") (pintype "passive"))
      (node (ref "V4") (pin "C") (pinfunction "C_C") (pintype "passive"))
    )
    (net (code "67") (name "/S3") (class "Default")
      (node (ref "Q1") (pin "8") (pinfunction "L_3_8") (pintype "passive"))
      (node (ref "V5") (pin "C") (pinfunction "C_C") (pintype "passive"))
    )
    (net (code "68") (name "/S4") (class "Default")
      (node (ref "Q1") (pin "6") (pinfunction "L_4_6") (pintype "passive"))
      (node (ref "V6") (pin "C") (pinfunction "C_C") (pintype "passive"))
    )
    (net (code "69") (name "/SP_CS") (class "Default")
      (node (ref "JP13") (pin "1") (pinfunction "1_1") (pintype "passive"))
      (node (ref "R8") (pin "1") (pinfunction "1_1") (pintype "passive"))
      (node (ref "U7") (pin "1") (pinfunction "~{CS}_1") (pintype "passive"))
    )
    (net (code "70") (name "/SP_MISO") (class "Default")
      (node (ref "JP13") (pin "3") (pinfunction "3_3") (pintype "passive"))
      (node (ref "U7") (pin "2") (pinfunction "DO_2") (pintype "passive"))
    )
    (net (code "71") (name "/SP_MOSI") (class "Default")
      (node (ref "JP13") (pin "4") (pinfunction "4_4") (pintype "passive"))
      (node (ref "U7") (pin "5") (pinfunction "DI_5") (pintype "passive"))
    )
    (net (code "72") (name "/SP_SCK") (class "Default")
      (node (ref "JP13") (pin "2") (pinfunction "2_2") (pintype "passive"))
      (node (ref "U7") (pin "6") (pinfunction "CLK_6") (pintype "passive"))
    )
    (net (code "73") (name "/T2IN") (class "Default")
      (node (ref "JP6") (pin "2") (pinfunction "2_2") (pintype "passive"))
      (node (ref "U3") (pin "10") (pinfunction "T2IN_10") (pintype "passive"))
    )
    (net (code "74") (name "/VBAT") (class "Default")
      (node (ref "U1") (pin "1") (pinfunction "VBAT_1") (pintype "passive"))
    )
    (net (code "75") (name "3V3") (class "Default")
      (node (ref "B1") (pin "2") (pinfunction "-_2") (pintype "passive"))
      (node (ref "BEEP1") (pin "1") (pinfunction "+_1") (pintype "passive"))
      (node (ref "C1") (pin "1") (pinfunction "1_1") (pintype "passive"))
      (node (ref "C10") (pin "2") (pinfunction "2_2") (pintype "passive"))
      (node (ref "C11") (pin "1") (pinfunction "1_1") (pintype "passive"))
      (node (ref "C11") (pin "2") (pinfunction "2_2") (pintype "passive"))
      (node (ref "C12") (pin "1") (pinfunction "1_1") (pintype "passive"))
      (node (ref "C12") (pin "2") (pinfunction "2_2") (pintype "passive"))
      (node (ref "C13") (pin "1") (pinfunction "1_1") (pintype "passive"))
      (node (ref "C13") (pin "2") (pinfunction "2_2") (pintype "passive"))
      (node (ref "C16") (pin "1") (pinfunction "1_1") (pintype "passive"))
      (node (ref "C16") (pin "2") (pinfunction "2_2") (pintype "passive"))
      (node (ref "C17") (pin "2") (pinfunction "2_2") (pintype "passive"))
      (node (ref "C18") (pin "2") (pinfunction "2_2") (pintype "passive"))
      (node (ref "C19") (pin "1") (pinfunction "1_1") (pintype "passive"))
      (node (ref "C19") (pin "2") (pinfunction "2_2") (pintype "passive"))
      (node (ref "C2") (pin "2") (pinfunction "2_2") (pintype "passive"))
      (node (ref "C20") (pin "1") (pinfunction "1_1") (pintype "passive"))
      (node (ref "C20") (pin "2") (pinfunction "2_2") (pintype "passive"))
      (node (ref "C21") (pin "1") (pinfunction "1_1") (pintype "passive"))
      (node (ref "C21") (pin "2") (pinfunction "2_2") (pintype "passive"))
      (node (ref "C22") (pin "1") (pinfunction "1_1") (pintype "passive"))
      (node (ref "C22") (pin "2") (pinfunction "2_2") (pintype "passive"))
      (node (ref "C23") (pin "1") (pinfunction "1_1") (pintype "passive"))
      (node (ref "C23") (pin "2") (pinfunction "2_2") (pintype "passive"))
      (node (ref "C24") (pin "1") (pinfunction "1_1") (pintype "passive"))
      (node (ref "C24") (pin "2") (pinfunction "2_2") (pintype "passive"))
      (node (ref "C25") (pin "1") (pinfunction "1_1") (pintype "passive"))
      (node (ref "C25") (pin "2") (pinfunction "2_2") (pintype "passive"))
      (node (ref "C26") (pin "1") (pinfunction "1_1") (pintype "passive"))
      (node (ref "C26") (pin "2") (pinfunction "2_2") (pintype "passive"))
      (node (ref "C27") (pin "1") (pinfunction "1_1") (pintype "passive"))
      (node (ref "C27") (pin "2") (pinfunction "2_2") (pintype "passive"))
      (node (ref "C28") (pin "1") (pinfunction "1_1") (pintype "passive"))
      (node (ref "C28") (pin "2") (pinfunction "2_2") (pintype "passive"))
      (node (ref "C3") (pin "2") (pinfunction "2_2") (pintype "passive"))
      (node (ref "C4") (pin "2") (pinfunction "2_2") (pintype "passive"))
      (node (ref "C5") (pin "2") (pinfunction "2_2") (pintype "passive"))
      (node (ref "C6") (pin "1") (pinfunction "1_1") (pintype "passive"))
      (node (ref "C7") (pin "1") (pinfunction "1_1") (pintype "passive"))
      (node (ref "C8") (pin "1") (pinfunction "1_1") (pintype "passive"))
      (node (ref "C9") (pin "2") (pinfunction "2_2") (pintype "passive"))
      (node (ref "DB1") (pin "5") (pinfunction "5_5") (pintype "passive"))
      (node (ref "H1") (pin "2") (pinfunction "K_2") (pintype "passive"))
      (node (ref "JP1") (pin "1") (pinfunction "1_1") (pintype "passive"))
      (node (ref "JP1") (pin "3") (pinfunction "3_3") (pintype "passive"))
      (node (ref "JP2") (pin "1") (pinfunction "1_1") (pintype "passive"))
      (node (ref "JP2") (pin "3") (pinfunction "3_3") (pintype "passive"))
      (node (ref "KEY1") (pin "1") (pinfunction "1_1") (pintype "passive"))
      (node (ref "KEY1") (pin "3") (pinfunction "3_3") (pintype "passive"))
      (node (ref "KEY2") (pin "1") (pinfunction "1_1") (pintype "passive"))
      (node (ref "KEY2") (pin "3") (pinfunction "3_3") (pintype "passive"))
      (node (ref "KEY3") (pin "1") (pinfunction "1_1") (pintype "passive"))
      (node (ref "KEY3") (pin "3") (pinfunction "3_3") (pintype "passive"))
      (node (ref "KEY4") (pin "1") (pinfunction "1_1") (pintype "passive"))
      (node (ref "KEY4") (pin "3") (pinfunction "3_3") (pintype "passive"))
      (node (ref "LCD1") (pin "1") (pinfunction "GND_1") (pintype "passive"))
      (node (ref "LCD1") (pin "2") (pinfunction "3V3_2") (pintype "passive"))
      (node (ref "N1") (pin "1") (pinfunction "GND_1") (pintype "passive"))
      (node (ref "N1") (pin "2") (pinfunction "VOUT_2") (pintype "passive"))
      (node (ref "N1") (pin "4") (pinfunction "VOUT_4") (pintype "passive"))
      (node (ref "R1") (pin "2") (pinfunction "2_2") (pintype "passive"))
      (node (ref "R11") (pin "2") (pinfunction "2_2") (pintype "passive"))
      (node (ref "R12") (pin "1") (pinfunction "1_1") (pintype "passive"))
      (node (ref "R13") (pin "1") (pinfunction "1_1") (pintype "passive"))
      (node (ref "R14") (pin "1") (pinfunction "1_1") (pintype "passive"))
      (node (ref "R15") (pin "1") (pinfunction "1_1") (pintype "passive"))
      (node (ref "R16") (pin "2") (pinfunction "2_2") (pintype "passive"))
      (node (ref "R17") (pin "2") (pinfunction "2_2") (pintype "passive"))
      (node (ref "R18") (pin "2") (pinfunction "2_2") (pintype "passive"))
      (node (ref "R19") (pin "2") (pinfunction "2_2") (pintype "passive"))
      (node (ref "R20") (pin "2") (pinfunction "2_2") (pintype "passive"))
      (node (ref "R21") (pin "1") (pinfunction "1_1") (pintype "passive"))
      (node (ref "R22") (pin "1") (pinfunction "1_1") (pintype "passive"))
      (node (ref "R23") (pin "2") (pinfunction "2_2") (pintype "passive"))
      (node (ref "R24") (pin "2") (pinfunction "2_2") (pintype "passive"))
      (node (ref "R25") (pin "2") (pinfunction "2_2") (pintype "passive"))
      (node (ref "R26") (pin "2") (pinfunction "2_2") (pintype "passive"))
      (node (ref "R4") (pin "1") (pinfunction "1_1") (pintype "passive"))
      (node (ref "R5") (pin "2") (pinfunction "2_2") (pintype "passive"))
      (node (ref "R6") (pin "1") (pinfunction "1_1") (pintype "passive"))
      (node (ref "R8") (pin "2") (pinfunction "2_2") (pintype "passive"))
      (node (ref "R9") (pin "1") (pinfunction "1_1") (pintype "passive"))
      (node (ref "U1") (pin "23") (pinfunction "VSS_1_23") (pintype "passive"))
      (node (ref "U1") (pin "24") (pinfunction "VDD_1_24") (pintype "passive"))
      (node (ref "U1") (pin "35") (pinfunction "VSS_2_35") (pintype "passive"))
      (node (ref "U1") (pin "36") (pinfunction "VDD_2_36") (pintype "passive"))
      (node (ref "U1") (pin "47") (pinfunction "VSS_3_47") (pintype "passive"))
      (node (ref "U1") (pin "48") (pinfunction "VDD_3_48") (pintype "passive"))
      (node (ref "U1") (pin "8") (pinfunction "VSSA_8") (pintype "passive"))
      (node (ref "U1") (pin "9") (pinfunction "VDDA_9") (pintype "passive"))
      (node (ref "U10") (pin "13") (pinfunction "~{EN}_13") (pintype "passive"))
      (node (ref "U10") (pin "16") (pinfunction "VCC_16") (pintype "passive"))
      (node (ref "U10") (pin "8") (pinfunction "GND_8") (pintype "passive"))
      (node (ref "U2") (pin "1") (pinfunction "GND_1") (pintype "passive"))
      (node (ref "U2") (pin "16") (pinfunction "VCC_16") (pintype "passive"))
      (node (ref "U2") (pin "4") (pinfunction "V3_4") (pintype "passive"))
      (node (ref "U3") (pin "15") (pinfunction "GND_15") (pintype "passive"))
      (node (ref "U3") (pin "16") (pinfunction "VCC_16") (pintype "passive"))
      (node (ref "U4") (pin "5") (pinfunction "GND_5") (pintype "passive"))
      (node (ref "U4") (pin "8") (pinfunction "VCC_8") (pintype "passive"))
      (node (ref "U5") (pin "2") (pinfunction "GND_2") (pintype "passive"))
      (node (ref "U5") (pin "3") (pinfunction "VCC_3") (pintype "passive"))
      (node (ref "U5") (pin "8") (pinfunction "Rs_8") (pintype "passive"))
      (node (ref "U6") (pin "1") (pinfunction "A0_1") (pintype "passive"))
      (node (ref "U6") (pin "2") (pinfunction "A1_2") (pintype "passive"))
      (node (ref "U6") (pin "3") (pinfunction "A2_3") (pintype "passive"))
      (node (ref "U6") (pin "4") (pinfunction "GND_4") (pintype "passive"))
      (node (ref "U6") (pin "7") (pinfunction "WP_7") (pintype "passive"))
      (node (ref "U6") (pin "8") (pinfunction "VCC_8") (pintype "passive"))
      (node (ref "U7") (pin "3") (pinfunction "~{WP}_3") (pintype "passive"))
      (node (ref "U7") (pin "4") (pinfunction "GND_4") (pintype "passive"))
      (node (ref "U7") (pin "7") (pinfunction "~{HOLD}_7") (pintype "passive"))
      (node (ref "U7") (pin "8") (pinfunction "VCC_8") (pintype "passive"))
      (node (ref "U8") (pin "1") (pinfunction "GND_1") (pintype "passive"))
      (node (ref "U8") (pin "2") (pinfunction "VCC_2") (pintype "passive"))
      (node (ref "U9") (pin "13") (pinfunction "~{EN}_13") (pintype "passive"))
      (node (ref "U9") (pin "16") (pinfunction "VCC_16") (pintype "passive"))
      (node (ref "U9") (pin "8") (pinfunction "GND_8") (pintype "passive"))
      (node (ref "USB1") (pin "5") (pinfunction "GND_5") (pintype "passive"))
      (node (ref "USB2") (pin "5") (pinfunction "GND_5") (pintype "passive"))
      (node (ref "V1") (pin "E") (pinfunction "E_E") (pintype "passive"))
      (node (ref "V2") (pin "E") (pinfunction "E_E") (pintype "passive"))
      (node (ref "X4") (pin "1") (pinfunction "1_1") (pintype "passive"))
      (node (ref "X4") (pin "2") (pinfunction "2_2") (pintype "passive"))
      (node (ref "X4") (pin "3") (pinfunction "3_3") (pintype "passive"))
      (node (ref "X5") (pin "1") (pinfunction "1_1") (pintype "passive"))
      (node (ref "X5") (pin "2") (pinfunction "2_2") (pintype "passive"))
      (node (ref "X5") (pin "3") (pinfunction "3_3") (pintype "passive"))
      (node (ref "X6") (pin "1") (pinfunction "1_1") (pintype "passive"))
      (node (ref "X6") (pin "2") (pinfunction "2_2") (pintype "passive"))
      (node (ref "X6") (pin "3") (pinfunction "3_3") (pintype "passive"))
      (node (ref "Z1") (pin "1") (pinfunction "1_1") (pintype "passive"))
    )
    (net (code "76") (name "5V") (class "Default")
      (node (ref "C10") (pin "1") (pinfunction "1_1") (pintype "passive"))
      (node (ref "C9") (pin "1") (pinfunction "1_1") (pintype "passive"))
      (node (ref "N1") (pin "3") (pinfunction "VIN_3") (pintype "passive"))
      (node (ref "S1") (pin "3") (pintype "passive"))
      (node (ref "X3") (pin "1") (pinfunction "1_1") (pintype "passive"))
      (node (ref "X3") (pin "2") (pinfunction "2_2") (pintype "passive"))
      (node (ref "X3") (pin "3") (pinfunction "3_3") (pintype "passive"))
    )
    (net (code "77") (name "Net-(B1-+)") (class "Default")
      (node (ref "B1") (pin "1") (pinfunction "+_1") (pintype "passive"))
      (node (ref "D1") (pin "1") (pinfunction "A_1") (pintype "passive"))
    )
    (net (code "78") (name "Net-(BEEP1--)") (class "Default")
      (node (ref "BEEP1") (pin "2") (pinfunction "-_2") (pintype "passive"))
      (node (ref "V2") (pin "C") (pinfunction "C_C") (pintype "passive"))
    )
    (net (code "79") (name "Net-(D1-K)") (class "Default")
      (node (ref "C8") (pin "2") (pinfunction "2_2") (pintype "passive"))
      (node (ref "D1") (pin "2") (pinfunction "K_2") (pintype "passive"))
      (node (ref "D2") (pin "2") (pinfunction "K_2") (pintype "passive"))
    )
    (net (code "80") (name "Net-(H1-A)") (class "Default")
      (node (ref "H1") (pin "1") (pinfunction "A_1") (pintype "passive"))
      (node (ref "R9") (pin "2") (pinfunction "2_2") (pintype "passive"))
    )
    (net (code "81") (name "Net-(H2-A)") (class "Default")
      (node (ref "H2") (pin "1") (pinfunction "A_1") (pintype "passive"))
      (node (ref "R12") (pin "2") (pinfunction "2_2") (pintype "passive"))
    )
    (net (code "82") (name "Net-(H2-K)") (class "Default")
      (node (ref "H2") (pin "2") (pinfunction "K_2") (pintype "passive"))
      (node (ref "JP16") (pin "1") (pinfunction "1_1") (pintype "passive"))
    )
    (net (code "83") (name "Net-(H3-A)") (class "Default")
      (node (ref "H3") (pin "1") (pinfunction "A_1") (pintype "passive"))
      (node (ref "R13") (pin "2") (pinfunction "2_2") (pintype "passive"))
    )
    (net (code "84") (name "Net-(H3-K)") (class "Default")
      (node (ref "H3") (pin "2") (pinfunction "K_2") (pintype "passive"))
      (node (ref "JP16") (pin "2") (pinfunction "2_2") (pintype "passive"))
    )
    (net (code "85") (name "Net-(H4-A)") (class "Default")
      (node (ref "H4") (pin "1") (pinfunction "A_1") (pintype "passive"))
      (node (ref "R14") (pin "2") (pinfunction "2_2") (pintype "passive"))
    )
    (net (code "86") (name "Net-(H4-K)") (class "Default")
      (node (ref "H4") (pin "2") (pinfunction "K_2") (pintype "passive"))
      (node (ref "JP16") (pin "3") (pinfunction "3_3") (pintype "passive"))
    )
    (net (code "87") (name "Net-(H5-A)") (class "Default")
      (node (ref "H5") (pin "1") (pinfunction "A_1") (pintype "passive"))
      (node (ref "R15") (pin "2") (pinfunction "2_2") (pintype "passive"))
    )
    (net (code "88") (name "Net-(H5-K)") (class "Default")
      (node (ref "H5") (pin "2") (pinfunction "K_2") (pintype "passive"))
      (node (ref "JP16") (pin "4") (pinfunction "4_4") (pintype "passive"))
    )
    (net (code "89") (name "Net-(JP1-Pad2)") (class "Default")
      (node (ref "JP1") (pin "2") (pinfunction "2_2") (pintype "passive"))
      (node (ref "R2") (pin "2") (pinfunction "2_2") (pintype "passive"))
    )
    (net (code "90") (name "Net-(JP2-Pad2)") (class "Default")
      (node (ref "JP2") (pin "2") (pinfunction "2_2") (pintype "passive"))
      (node (ref "R3") (pin "2") (pinfunction "2_2") (pintype "passive"))
    )
    (net (code "91") (name "Net-(JP15-Pad1)") (class "Default")
      (node (ref "JP15") (pin "1") (pinfunction "1_1") (pintype "passive"))
      (node (ref "R7") (pin "1") (pinfunction "1_1") (pintype "passive"))
    )
    (net (code "92") (name "Net-(R6-Pad2)") (class "Default")
      (node (ref "R6") (pin "2") (pinfunction "2_2") (pintype "passive"))
      (node (ref "R7") (pin "2") (pinfunction "2_2") (pintype "passive"))
      (node (ref "V2") (pin "B") (pinfunction "B_B") (pintype "passive"))
    )
    (net (code "93") (name "Net-(R10-Pad2)") (class "Default")
      (node (ref "R10") (pin "2") (pinfunction "2_2") (pintype "passive"))
      (node (ref "V1") (pin "B") (pinfunction "B_B") (pintype "passive"))
    )
    (net (code "94") (name "Net-(R23-Pad1)") (class "Default")
      (node (ref "R23") (pin "1") (pinfunction "1_1") (pintype "passive"))
      (node (ref "V3") (pin "E") (pinfunction "E_E") (pintype "passive"))
    )
    (net (code "95") (name "Net-(R24-Pad1)") (class "Default")
      (node (ref "R24") (pin "1") (pinfunction "1_1") (pintype "passive"))
      (node (ref "V4") (pin "E") (pinfunction "E_E") (pintype "passive"))
    )
    (net (code "96") (name "Net-(R25-Pad1)") (class "Default")
      (node (ref "R25") (pin "1") (pinfunction "1_1") (pintype "passive"))
      (node (ref "V5") (pin "E") (pinfunction "E_E") (pintype "passive"))
    )
    (net (code "97") (name "Net-(R26-Pad1)") (class "Default")
      (node (ref "R26") (pin "1") (pinfunction "1_1") (pintype "passive"))
      (node (ref "V6") (pin "E") (pinfunction "E_E") (pintype "passive"))
    )
    (net (code "98") (name "Net-(R27-Pad2)") (class "Default")
      (node (ref "R27") (pin "2") (pintype "passive"))
      (node (ref "V3") (pin "B") (pinfunction "B_B") (pintype "passive"))
    )
    (net (code "99") (name "Net-(R28-Pad2)") (class "Default")
      (node (ref "R28") (pin "2") (pintype "passive"))
      (node (ref "V4") (pin "B") (pinfunction "B_B") (pintype "passive"))
    )
    (net (code "100") (name "Net-(R29-Pad2)") (class "Default")
      (node (ref "R29") (pin "2") (pintype "passive"))
      (node (ref "V5") (pin "B") (pinfunction "B_B") (pintype "passive"))
    )
    (net (code "101") (name "Net-(R30-Pad2)") (class "Default")
      (node (ref "R30") (pin "2") (pintype "passive"))
      (node (ref "V6") (pin "B") (pinfunction "B_B") (pintype "passive"))
    )
    (net (code "102") (name "Net-(U2-UD+)") (class "Default")
      (node (ref "U2") (pin "5") (pinfunction "UD+_5") (pintype "passive"))
      (node (ref "USB1") (pin "3") (pinfunction "D+_3") (pintype "passive"))
    )
    (net (code "103") (name "Net-(U2-UD-)") (class "Default")
      (node (ref "U2") (pin "6") (pinfunction "UD-_6") (pintype "passive"))
      (node (ref "USB1") (pin "2") (pinfunction "D-_2") (pintype "passive"))
    )
    (net (code "104") (name "Net-(U2-~{RTS})") (class "Default")
      (node (ref "R10") (pin "1") (pinfunction "1_1") (pintype "passive"))
      (node (ref "U2") (pin "14") (pinfunction "~{RTS}_14") (pintype "passive"))
    )
    (net (code "105") (name "Net-(U3-C1+)") (class "Default")
      (node (ref "C14") (pin "2") (pinfunction "2_2") (pintype "passive"))
      (node (ref "U3") (pin "1") (pinfunction "C1+_1") (pintype "passive"))
    )
    (net (code "106") (name "Net-(U3-C1-)") (class "Default")
      (node (ref "C14") (pin "1") (pinfunction "1_1") (pintype "passive"))
      (node (ref "U3") (pin "3") (pinfunction "C1-_3") (pintype "passive"))
    )
    (net (code "107") (name "Net-(U3-C2+)") (class "Default")
      (node (ref "C15") (pin "2") (pinfunction "2_2") (pintype "passive"))
      (node (ref "U3") (pin "4") (pinfunction "C2+_4") (pintype "passive"))
    )
    (net (code "108") (name "Net-(U3-C2-)") (class "Default")
      (node (ref "C15") (pin "1") (pinfunction "1_1") (pintype "passive"))
      (node (ref "U3") (pin "5") (pinfunction "C2-_5") (pintype "passive"))
    )
    (net (code "109") (name "Net-(U3-R2IN)") (class "Default")
      (node (ref "DB1") (pin "3") (pinfunction "3_3") (pintype "passive"))
      (node (ref "U3") (pin "8") (pinfunction "R2IN_8") (pintype "passive"))
    )
    (net (code "110") (name "Net-(U3-V+)") (class "Default")
      (node (ref "C18") (pin "1") (pinfunction "1_1") (pintype "passive"))
      (node (ref "U3") (pin "2") (pinfunction "V+_2") (pintype "passive"))
    )
    (net (code "111") (name "Net-(U3-V-)") (class "Default")
      (node (ref "C17") (pin "1") (pinfunction "1_1") (pintype "passive"))
      (node (ref "U3") (pin "6") (pinfunction "V-_6") (pintype "passive"))
    )
    (net (code "112") (name "Net-(U4-A)") (class "Default")
      (node (ref "R17") (pin "1") (pinfunction "1_1") (pintype "passive"))
      (node (ref "U4") (pin "6") (pinfunction "A_6") (pintype "passive"))
      (node (ref "X7") (pin "2") (pinfunction "2_2") (pintype "passive"))
    )
    (net (code "113") (name "Net-(U4-B)") (class "Default")
      (node (ref "R16") (pin "1") (pinfunction "1_1") (pintype "passive"))
      (node (ref "U4") (pin "7") (pinfunction "B_7") (pintype "passive"))
      (node (ref "X7") (pin "1") (pinfunction "1_1") (pintype "passive"))
    )
    (net (code "114") (name "Net-(U4-DE)") (class "Default")
      (node (ref "JP8") (pin "1") (pinfunction "1_1") (pintype "passive"))
      (node (ref "U4") (pin "2") (pinfunction "~{RE}_2") (pintype "passive"))
      (node (ref "U4") (pin "3") (pinfunction "DE_3") (pintype "passive"))
    )
    (net (code "115") (name "Net-(U4-DI)") (class "Default")
      (node (ref "JP8") (pin "2") (pinfunction "2_2") (pintype "passive"))
      (node (ref "U4") (pin "4") (pinfunction "DI_4") (pintype "passive"))
    )
    (net (code "116") (name "Net-(U4-RO)") (class "Default")
      (node (ref "JP8") (pin "3") (pinfunction "3_3") (pintype "passive"))
      (node (ref "U4") (pin "1") (pinfunction "RO_1") (pintype "passive"))
    )
    (net (code "117") (name "Net-(U5-CANH)") (class "Default")
      (node (ref "U5") (pin "7") (pinfunction "CANH_7") (pintype "passive"))
      (node (ref "X8") (pin "1") (pinfunction "1_1") (pintype "passive"))
    )
    (net (code "118") (name "Net-(U5-CANL)") (class "Default")
      (node (ref "U5") (pin "6") (pinfunction "CANL_6") (pintype "passive"))
      (node (ref "X8") (pin "2") (pinfunction "2_2") (pintype "passive"))
    )
    (net (code "119") (name "Net-(U5-RXD)") (class "Default")
      (node (ref "JP10") (pin "2") (pinfunction "2_2") (pintype "passive"))
      (node (ref "U5") (pin "4") (pinfunction "RXD_4") (pintype "passive"))
    )
    (net (code "120") (name "Net-(U5-TXD)") (class "Default")
      (node (ref "JP10") (pin "1") (pinfunction "1_1") (pintype "passive"))
      (node (ref "U5") (pin "1") (pinfunction "TXD_1") (pintype "passive"))
    )
    (net (code "121") (name "Net-(U9-RESET)") (class "Default")
      (node (ref "R21") (pin "2") (pinfunction "2_2") (pintype "passive"))
      (node (ref "U9") (pin "10") (pinfunction "RESET_10") (pintype "passive"))
    )
    (net (code "122") (name "Net-(U10-RESET)") (class "Default")
      (node (ref "R22") (pin "2") (pinfunction "2_2") (pintype "passive"))
      (node (ref "U10") (pin "10") (pinfunction "RESET_10") (pintype "passive"))
    )
    (net (code "123") (name "Net-(USB2-D+)") (class "Default")
      (node (ref "JP18") (pin "2") (pinfunction "2_2") (pintype "passive"))
      (node (ref "R20") (pin "1") (pinfunction "1_1") (pintype "passive"))
      (node (ref "USB2") (pin "3") (pinfunction "D+_3") (pintype "passive"))
    )
    (net (code "124") (name "Net-(USB2-D-)") (class "Default")
      (node (ref "JP18") (pin "1") (pinfunction "1_1") (pintype "passive"))
      (node (ref "USB2") (pin "2") (pinfunction "D-_2") (pintype "passive"))
    )
    (net (code "125") (name "VUSB") (class "Default")
      (node (ref "S1") (pin "2") (pintype "passive"))
      (node (ref "USB1") (pin "1") (pinfunction "VCC_1") (pintype "passive"))
      (node (ref "USB2") (pin "1") (pinfunction "VCC_1") (pintype "passive"))
    )
    (net (code "126") (name "unconnected-(D2-A-Pad1)") (class "Default")
      (node (ref "D2") (pin "1") (pinfunction "A_1") (pintype "passive"))
    )
    (net (code "127") (name "unconnected-(DB1-Pad1)") (class "Default")
      (node (ref "DB1") (pin "1") (pinfunction "1_1") (pintype "passive"))
    )
    (net (code "128") (name "unconnected-(DB1-Pad2)") (class "Default")
      (node (ref "DB1") (pin "2") (pinfunction "2_2") (pintype "passive"))
    )
    (net (code "129") (name "unconnected-(DB1-Pad4)") (class "Default")
      (node (ref "DB1") (pin "4") (pinfunction "4_4") (pintype "passive"))
    )
    (net (code "130") (name "unconnected-(DB1-Pad6)") (class "Default")
      (node (ref "DB1") (pin "6") (pinfunction "6_6") (pintype "passive"))
    )
    (net (code "131") (name "unconnected-(DB1-Pad7)") (class "Default")
      (node (ref "DB1") (pin "7") (pinfunction "7_7") (pintype "passive"))
    )
    (net (code "132") (name "unconnected-(DB1-Pad8)") (class "Default")
      (node (ref "DB1") (pin "8") (pinfunction "8_8") (pintype "passive"))
    )
    (net (code "133") (name "unconnected-(DB1-Pad9)") (class "Default")
      (node (ref "DB1") (pin "9") (pinfunction "9_9") (pintype "passive"))
    )
    (net (code "134") (name "unconnected-(LCD1-DB0-Pad10)") (class "Default")
      (node (ref "LCD1") (pin "10") (pinfunction "DB0_10") (pintype "passive"))
    )
    (net (code "135") (name "unconnected-(LCD1-DB1-Pad11)") (class "Default")
      (node (ref "LCD1") (pin "11") (pinfunction "DB1_11") (pintype "passive"))
    )
    (net (code "136") (name "unconnected-(LCD1-DB2-Pad12)") (class "Default")
      (node (ref "LCD1") (pin "12") (pinfunction "DB2_12") (pintype "passive"))
    )
    (net (code "137") (name "unconnected-(LCD1-DB3-Pad13)") (class "Default")
      (node (ref "LCD1") (pin "13") (pinfunction "DB3_13") (pintype "passive"))
    )
    (net (code "138") (name "unconnected-(LCD1-DB4-Pad14)") (class "Default")
      (node (ref "LCD1") (pin "14") (pinfunction "DB4_14") (pintype "passive"))
    )
    (net (code "139") (name "unconnected-(LCD1-DB5-Pad15)") (class "Default")
      (node (ref "LCD1") (pin "15") (pinfunction "DB5_15") (pintype "passive"))
    )
    (net (code "140") (name "unconnected-(LCD1-DB6-Pad16)") (class "Default")
      (node (ref "LCD1") (pin "16") (pinfunction "DB6_16") (pintype "passive"))
    )
    (net (code "141") (name "unconnected-(LCD1-DB7-Pad17)") (class "Default")
      (node (ref "LCD1") (pin "17") (pinfunction "DB7_17") (pintype "passive"))
    )
    (net (code "142") (name "unconnected-(LCD1-LCD_MISO-Pad8)") (class "Default")
      (node (ref "LCD1") (pin "8") (pinfunction "LCD_MISO_8") (pintype "passive"))
    )
    (net (code "143") (name "unconnected-(LCD1-LCD_MOSI-Pad7)") (class "Default")
      (node (ref "LCD1") (pin "7") (pinfunction "LCD_MOSI_7") (pintype "passive"))
    )
    (net (code "144") (name "unconnected-(LCD1-XPT_BUSY-Pad30)") (class "Default")
      (node (ref "LCD1") (pin "30") (pinfunction "XPT_BUSY_30") (pintype "passive"))
    )
    (net (code "145") (name "unconnected-(S1-Pad1)") (class "Default")
      (node (ref "S1") (pin "1") (pintype "passive"))
    )
    (net (code "146") (name "unconnected-(S1-Pad4)") (class "Default")
      (node (ref "S1") (pin "4") (pintype "passive"))
    )
    (net (code "147") (name "unconnected-(S1-Pad5)") (class "Default")
      (node (ref "S1") (pin "5") (pintype "passive"))
    )
    (net (code "148") (name "unconnected-(S1-Pad6)") (class "Default")
      (node (ref "S1") (pin "6") (pintype "passive"))
    )
    (net (code "149") (name "unconnected-(U2-R232-Pad15)") (class "Default")
      (node (ref "U2") (pin "15") (pinfunction "R232_15") (pintype "passive"))
    )
    (net (code "150") (name "unconnected-(U2-~{CTS}-Pad9)") (class "Default")
      (node (ref "U2") (pin "9") (pinfunction "~{CTS}_9") (pintype "passive"))
    )
    (net (code "151") (name "unconnected-(U2-~{DCD}-Pad12)") (class "Default")
      (node (ref "U2") (pin "12") (pinfunction "~{DCD}_12") (pintype "passive"))
    )
    (net (code "152") (name "unconnected-(U2-~{DSR}-Pad10)") (class "Default")
      (node (ref "U2") (pin "10") (pinfunction "~{DSR}_10") (pintype "passive"))
    )
    (net (code "153") (name "unconnected-(U2-~{RI}-Pad11)") (class "Default")
      (node (ref "U2") (pin "11") (pinfunction "~{RI}_11") (pintype "passive"))
    )
    (net (code "154") (name "unconnected-(U3-R1IN-Pad13)") (class "Default")
      (node (ref "U3") (pin "13") (pinfunction "R1IN_13") (pintype "passive"))
    )
    (net (code "155") (name "unconnected-(U3-R1OUT-Pad12)") (class "Default")
      (node (ref "U3") (pin "12") (pinfunction "R1OUT_12") (pintype "passive"))
    )
    (net (code "156") (name "unconnected-(U3-T1IN-Pad11)") (class "Default")
      (node (ref "U3") (pin "11") (pinfunction "T1IN_11") (pintype "passive"))
    )
    (net (code "157") (name "unconnected-(U3-T1OUT-Pad14)") (class "Default")
      (node (ref "U3") (pin "14") (pinfunction "T1OUT_14") (pintype "passive"))
    )
    (net (code "158") (name "unconnected-(U3-T2OUT-Pad7)") (class "Default")
      (node (ref "U3") (pin "7") (pinfunction "T2OUT_7") (pintype "passive"))
    )
    (net (code "159") (name "unconnected-(U5-Vref-Pad5)") (class "Default")
      (node (ref "U5") (pin "5") (pinfunction "Vref_5") (pintype "passive"))
    )
    (net (code "160") (name "unconnected-(U10-QE-Pad4)") (class "Default")
      (node (ref "U10") (pin "4") (pinfunction "QE_4") (pintype "passive"))
    )
    (net (code "161") (name "unconnected-(U10-QF-Pad5)") (class "Default")
      (node (ref "U10") (pin "5") (pinfunction "QF_5") (pintype "passive"))
    )
    (net (code "162") (name "unconnected-(U10-QG-Pad6)") (class "Default")
      (node (ref "U10") (pin "6") (pinfunction "QG_6") (pintype "passive"))
    )
    (net (code "163") (name "unconnected-(U10-QH-Pad7)") (class "Default")
      (node (ref "U10") (pin "7") (pinfunction "QH_7") (pintype "passive"))
    )
    (net (code "164") (name "unconnected-(U10-SQH-Pad9)") (class "Default")
      (node (ref "U10") (pin "9") (pinfunction "SQH_9") (pintype "passive"))
    )
    (net (code "165") (name "unconnected-(USB1-NC-Pad4)") (class "Default")
      (node (ref "USB1") (pin "4") (pinfunction "NC_4") (pintype "passive"))
    )
    (net (code "166") (name "unconnected-(USB2-NC-Pad4)") (class "Default")
      (node (ref "USB2") (pin "4") (pinfunction "NC_4") (pintype "passive"))
    )
    (net (code "167") (name "unconnected-(Z1-Pad2)") (class "Default")
      (node (ref "Z1") (pin "2") (pinfunction "2_2") (pintype "passive"))
    )
    (net (code "168") (name "unconnected-(Z1-Pad3)") (class "Default")
      (node (ref "Z1") (pin "3") (pinfunction "3_3") (pintype "passive"))
    )
    (net (code "169") (name "unconnected-(Z1-Pad4)") (class "Default")
      (node (ref "Z1") (pin "4") (pinfunction "4_4") (pintype "passive"))
    )
    (net (code "170") (name "unconnected-(Z1-Pad6)") (class "Default")
      (node (ref "Z1") (pin "6") (pinfunction "6_6") (pintype "passive"))
    )
    (net (code "171") (name "unconnected-(Z1-Pad8)") (class "Default")
      (node (ref "Z1") (pin "8") (pinfunction "8_8") (pintype "passive"))
    )
    (net (code "172") (name "unconnected-(Z1-Pad10)") (class "Default")
      (node (ref "Z1") (pin "10") (pinfunction "10_10") (pintype "passive"))
    )
    (net (code "173") (name "unconnected-(Z1-Pad11)") (class "Default")
      (node (ref "Z1") (pin "11") (pinfunction "11_11") (pintype "passive"))
    )
    (net (code "174") (name "unconnected-(Z1-Pad12)") (class "Default")
      (node (ref "Z1") (pin "12") (pinfunction "12_12") (pintype "passive"))
    )
    (net (code "175") (name "unconnected-(Z1-Pad14)") (class "Default")
      (node (ref "Z1") (pin "14") (pinfunction "14_14") (pintype "passive"))
    )
    (net (code "176") (name "unconnected-(Z1-Pad16)") (class "Default")
      (node (ref "Z1") (pin "16") (pinfunction "16_16") (pintype "passive"))
    )
    (net (code "177") (name "unconnected-(Z1-Pad17)") (class "Default")
      (node (ref "Z1") (pin "17") (pinfunction "17_17") (pintype "passive"))
    )
    (net (code "178") (name "unconnected-(Z1-Pad18)") (class "Default")
      (node (ref "Z1") (pin "18") (pinfunction "18_18") (pintype "passive"))
    )
    (net (code "179") (name "unconnected-(Z1-Pad19)") (class "Default")
      (node (ref "Z1") (pin "19") (pinfunction "19_19") (pintype "passive"))
    )
    (net (code "180") (name "unconnected-(Z1-Pad20)") (class "Default")
      (node (ref "Z1") (pin "20") (pinfunction "20_20") (pintype "passive"))
    )
  )
)
